# Buck_Converter_schm.net
KiCad netlist of a schematic drawn in EAGLE
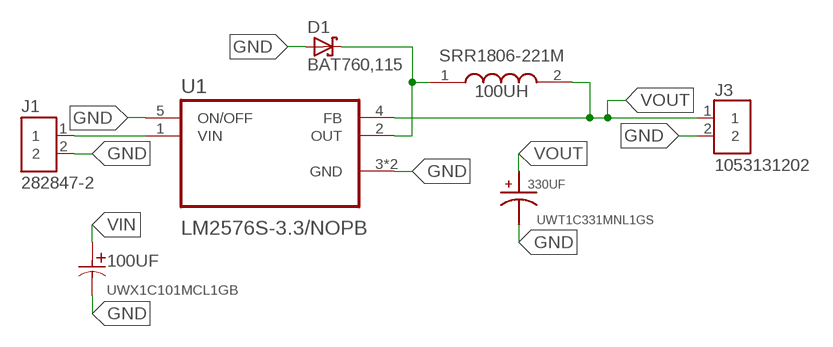
[diagram p0: schematic, sheet 1]

(export (version "E")
  (design (tool "Eeschema 10.0.6"))
  (components
    (comp (ref "100UF")
      (value "UWX1C101MCL1GB")
      (footprint "eagle-import:PCAP_6.3X5.4-ELECT_NCA")
      (libsource (lib "eagle-import") (part "UWX1C101MCL1GB"))
    )
    (comp (ref "100UH")
      (value "SRR1806-221M")
      (footprint "eagle-import:SRR1806221M")
      (fields (field (name "MOUSER_PART_NUMBER") "652-SRR1806-221M"))
      (libsource (lib "eagle-import") (part "SRR1806-221M"))
    )
    (comp (ref "330UF")
      (value "UWT1C331MNL1GS")
      (footprint "eagle-import:CAPAE830X1080N")
      (fields (field (name "DIGI-KEY_PART_NUMBER") "493-2180-1-ND") (field (name "MF") "Nichicon"))
      (libsource (lib "eagle-import") (part "UWT1C331MNL1GS"))
    )
    (comp (ref "D1")
      (value "BAT760,115")
      (footprint "eagle-import:SOD323(F)")
      (fields (field (name "MF") "Nexperia USA"))
      (libsource (lib "eagle-import") (part "BAT760,115"))
    )
    (comp (ref "J1")
      (value "282847-2")
      (footprint "eagle-import:TE_282847-2")
      (fields (field (name "MF") "TE Connectivity"))
      (libsource (lib "eagle-import") (part "282847-2"))
    )
    (comp (ref "J3")
      (value "1053131202")
      (footprint "eagle-import:MOLEX_1053131202")
      (fields (field (name "MF") "Molex"))
      (libsource (lib "eagle-import") (part "1053131202"))
    )
    (comp (ref "U1")
      (value "LM2576S-3.3/NOPB")
      (footprint "eagle-import:VREG_TPS79625KTTR")
      (fields (field (name "MF") "Texas Instruments"))
      (libsource (lib "eagle-import") (part "LM2576S-3.3/NOPB"))
    )
  )
  (nets
    (net (code "1") (name "GND") (class "Default")
      (node (ref "100UF") (pin "2") (pinfunction "2_2") (pintype "passive"))
      (node (ref "330UF") (pin "2") (pinfunction "2_2") (pintype "passive"))
      (node (ref "D1") (pin "2") (pinfunction "A_2") (pintype "passive"))
      (node (ref "J1") (pin "2") (pinfunction "2_2") (pintype "passive"))
      (node (ref "J3") (pin "2") (pinfunction "2_2") (pintype "passive"))
      (node (ref "U1") (pin "3") (pinfunction "GND_3") (pintype "power_in"))
      (node (ref "U1") (pin "5") (pinfunction "ON/OFF_5") (pintype "input"))
      (node (ref "U1") (pin "6") (pinfunction "GND_6") (pintype "power_in"))
    )
    (net (code "2") (name "Net-(D1-K)") (class "Default")
      (node (ref "100UH") (pin "1") (pinfunction "1_1") (pintype "bidirectional"))
      (node (ref "D1") (pin "1") (pinfunction "K_1") (pintype "passive"))
      (node (ref "U1") (pin "2") (pinfunction "OUT_2") (pintype "output"))
    )
    (net (code "3") (name "VIN") (class "Default")
      (node (ref "100UF") (pin "1") (pinfunction "1_1") (pintype "passive"))
      (node (ref "J1") (pin "1") (pinfunction "1_1") (pintype "passive"))
      (node (ref "U1") (pin "1") (pinfunction "VIN_1") (pintype "input"))
    )
    (net (code "4") (name "VOUT") (class "Default")
      (node (ref "100UH") (pin "2") (pinfunction "2_2") (pintype "bidirectional"))
      (node (ref "330UF") (pin "1") (pinfunction "1_1") (pintype "passive"))
      (node (ref "J3") (pin "1") (pinfunction "1_1") (pintype "passive"))
      (node (ref "U1") (pin "4") (pinfunction "FB_4") (pintype "output"))
    )
  )
)
